# Sheet1.net
KiCad netlist of a schematic drawn in Altium Designer
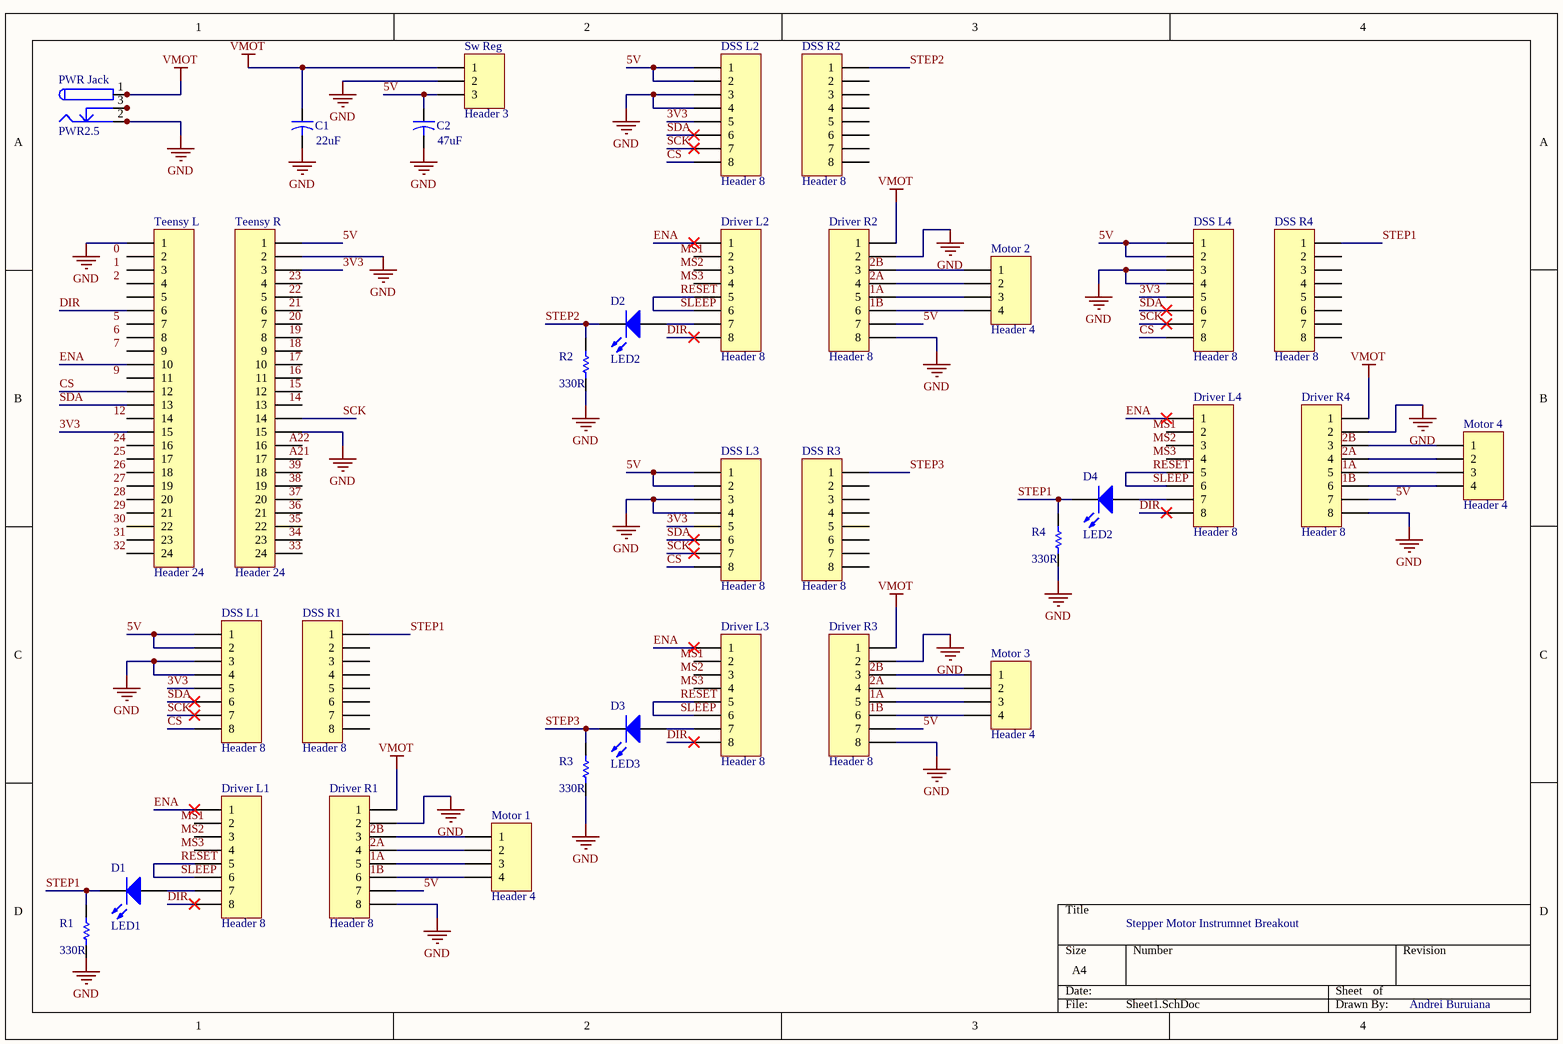
[diagram p0: Sheet1.SchDoc]

(export (version "E")
  (design (tool "Eeschema 10.0.6"))
  (components
    (comp (ref "C1")
      (value "22uF")
      (footprint "CAPR5-4X5")
      (description "Capacitor")
      (fields (field (name "PUBLISHER") "Altium Limited"))
      (libsource (lib "Miscellaneous Devices") (part "Cap2"))
    )
    (comp (ref "C2")
      (value "47uF")
      (footprint "CAPR5-4X5")
      (description "Capacitor")
      (fields (field (name "PUBLISHER") "Altium Limited"))
      (libsource (lib "Miscellaneous Devices") (part "Cap2"))
    )
    (comp (ref "D1")
      (value "LED1")
      (footprint "3.2X1.6X1.1")
      (description "Typical RED, GREEN, YELLOW, AMBER GaAs LED")
      (fields (field (name "PUBLISHER") "Altium Limited"))
      (libsource (lib "Miscellaneous Devices") (part "LED2"))
    )
    (comp (ref "D2")
      (value "LED2")
      (footprint "3.2X1.6X1.1")
      (description "Typical RED, GREEN, YELLOW, AMBER GaAs LED")
      (fields (field (name "PUBLISHER") "Altium Limited"))
      (libsource (lib "Miscellaneous Devices") (part "LED2"))
    )
    (comp (ref "D3")
      (value "LED3")
      (footprint "3.2X1.6X1.1")
      (description "Typical RED, GREEN, YELLOW, AMBER GaAs LED")
      (fields (field (name "PUBLISHER") "Altium Limited"))
      (libsource (lib "Miscellaneous Devices") (part "LED2"))
    )
    (comp (ref "D4")
      (value "LED2")
      (footprint "3.2X1.6X1.1")
      (description "Typical RED, GREEN, YELLOW, AMBER GaAs LED")
      (fields (field (name "PUBLISHER") "Altium Limited"))
      (libsource (lib "Miscellaneous Devices") (part "LED2"))
    )
    (comp (ref "Driver L1")
      (value "Header 8")
      (footprint "HDR1X8")
      (description "Header, 8-Pin")
      (fields (field (name "PUBLISHER") "Altium Limited"))
      (libsource (lib "") (part "Header 8_1"))
    )
    (comp (ref "Driver L2")
      (value "Header 8")
      (footprint "HDR1X8")
      (description "Header, 8-Pin")
      (fields (field (name "PUBLISHER") "Altium Limited"))
      (libsource (lib "") (part "Header 8_1"))
    )
    (comp (ref "Driver L3")
      (value "Header 8")
      (footprint "HDR1X8")
      (description "Header, 8-Pin")
      (fields (field (name "PUBLISHER") "Altium Limited"))
      (libsource (lib "") (part "Header 8_1"))
    )
    (comp (ref "Driver L4")
      (value "Header 8")
      (footprint "HDR1X8")
      (description "Header, 8-Pin")
      (fields (field (name "PUBLISHER") "Altium Limited"))
      (libsource (lib "") (part "Header 8_1"))
    )
    (comp (ref "Driver R1")
      (value "Header 8")
      (footprint "HDR1X8")
      (description "Header, 8-Pin")
      (fields (field (name "PUBLISHER") "Altium Limited"))
      (libsource (lib "Miscellaneous Connectors") (part "Header 8"))
    )
    (comp (ref "Driver R2")
      (value "Header 8")
      (footprint "HDR1X8")
      (description "Header, 8-Pin")
      (fields (field (name "PUBLISHER") "Altium Limited"))
      (libsource (lib "Miscellaneous Connectors") (part "Header 8"))
    )
    (comp (ref "Driver R3")
      (value "Header 8")
      (footprint "HDR1X8")
      (description "Header, 8-Pin")
      (fields (field (name "PUBLISHER") "Altium Limited"))
      (libsource (lib "Miscellaneous Connectors") (part "Header 8"))
    )
    (comp (ref "Driver R4")
      (value "Header 8")
      (footprint "HDR1X8")
      (description "Header, 8-Pin")
      (fields (field (name "PUBLISHER") "Altium Limited"))
      (libsource (lib "Miscellaneous Connectors") (part "Header 8"))
    )
    (comp (ref "DSS L1")
      (value "Header 8")
      (footprint "HDR1X8")
      (description "Header, 8-Pin")
      (fields (field (name "PUBLISHER") "Altium Limited"))
      (libsource (lib "") (part "Header 8_1"))
    )
    (comp (ref "DSS L2")
      (value "Header 8")
      (footprint "HDR1X8")
      (description "Header, 8-Pin")
      (fields (field (name "PUBLISHER") "Altium Limited"))
      (libsource (lib "") (part "Header 8_1"))
    )
    (comp (ref "DSS L3")
      (value "Header 8")
      (footprint "HDR1X8")
      (description "Header, 8-Pin")
      (fields (field (name "PUBLISHER") "Altium Limited"))
      (libsource (lib "") (part "Header 8_1"))
    )
    (comp (ref "DSS L4")
      (value "Header 8")
      (footprint "HDR1X8")
      (description "Header, 8-Pin")
      (fields (field (name "PUBLISHER") "Altium Limited"))
      (libsource (lib "") (part "Header 8_1"))
    )
    (comp (ref "DSS R1")
      (value "Header 8")
      (footprint "HDR1X8")
      (description "Header, 8-Pin")
      (fields (field (name "PUBLISHER") "Altium Limited"))
      (libsource (lib "Miscellaneous Connectors") (part "Header 8"))
    )
    (comp (ref "DSS R2")
      (value "Header 8")
      (footprint "HDR1X8")
      (description "Header, 8-Pin")
      (fields (field (name "PUBLISHER") "Altium Limited"))
      (libsource (lib "Miscellaneous Connectors") (part "Header 8"))
    )
    (comp (ref "DSS R3")
      (value "Header 8")
      (footprint "HDR1X8")
      (description "Header, 8-Pin")
      (fields (field (name "PUBLISHER") "Altium Limited"))
      (libsource (lib "Miscellaneous Connectors") (part "Header 8"))
    )
    (comp (ref "DSS R4")
      (value "Header 8")
      (footprint "HDR1X8")
      (description "Header, 8-Pin")
      (fields (field (name "PUBLISHER") "Altium Limited"))
      (libsource (lib "Miscellaneous Connectors") (part "Header 8"))
    )
    (comp (ref "Motor 1")
      (value "Header 4")
      (footprint "HDR1X4")
      (description "Header, 4-Pin")
      (fields (field (name "PUBLISHER") "Altium Limited"))
      (libsource (lib "Miscellaneous Connectors") (part "Header 4"))
    )
    (comp (ref "Motor 2")
      (value "Header 4")
      (footprint "HDR1X4")
      (description "Header, 4-Pin")
      (fields (field (name "PUBLISHER") "Altium Limited"))
      (libsource (lib "Miscellaneous Connectors") (part "Header 4"))
    )
    (comp (ref "Motor 3")
      (value "Header 4")
      (footprint "HDR1X4")
      (description "Header, 4-Pin")
      (fields (field (name "PUBLISHER") "Altium Limited"))
      (libsource (lib "Miscellaneous Connectors") (part "Header 4"))
    )
    (comp (ref "Motor 4")
      (value "Header 4")
      (footprint "HDR1X4")
      (description "Header, 4-Pin")
      (fields (field (name "PUBLISHER") "Altium Limited"))
      (libsource (lib "Miscellaneous Connectors") (part "Header 4"))
    )
    (comp (ref "PWR Jack")
      (value "PWR2.5")
      (footprint "KLD-0202")
      (description "Low Voltage Power Supply Connector")
      (fields (field (name "PUBLISHER") "Altium Limited"))
      (libsource (lib "Miscellaneous Connectors") (part "PWR2.5"))
    )
    (comp (ref "R1")
      (value "330R")
      (footprint "AXIAL-0.5")
      (description "Semiconductor Resistor")
      (fields (field (name "PUBLISHER") "Altium Limited"))
      (libsource (lib "Miscellaneous Devices") (part "Res Semi"))
    )
    (comp (ref "R2")
      (value "330R")
      (footprint "AXIAL-0.5")
      (description "Semiconductor Resistor")
      (fields (field (name "PUBLISHER") "Altium Limited"))
      (libsource (lib "Miscellaneous Devices") (part "Res Semi"))
    )
    (comp (ref "R3")
      (value "330R")
      (footprint "AXIAL-0.5")
      (description "Semiconductor Resistor")
      (fields (field (name "PUBLISHER") "Altium Limited"))
      (libsource (lib "Miscellaneous Devices") (part "Res Semi"))
    )
    (comp (ref "R4")
      (value "330R")
      (footprint "AXIAL-0.5")
      (description "Semiconductor Resistor")
      (fields (field (name "PUBLISHER") "Altium Limited"))
      (libsource (lib "Miscellaneous Devices") (part "Res Semi"))
    )
    (comp (ref "Sw Reg")
      (value "Header 3")
      (footprint "HDR1X3")
      (description "Header, 3-Pin")
      (fields (field (name "PUBLISHER") "Altium Limited"))
      (libsource (lib "Miscellaneous Connectors") (part "Header 3"))
    )
    (comp (ref "Teensy L")
      (value "Header 24")
      (footprint "HDR1X24")
      (description "Header, 24-Pin")
      (fields (field (name "PUBLISHER") "Altium Limited"))
      (libsource (lib "Miscellaneous Connectors") (part "Header 24"))
    )
    (comp (ref "Teensy R")
      (value "Header 24")
      (footprint "HDR1X24")
      (description "Header, 24-Pin")
      (fields (field (name "PUBLISHER") "Altium Limited"))
      (libsource (lib "") (part "Header 24_1"))
    )
  )
  (nets
    (net (code "8") (name "/3V3") (class "Default")
      (node (ref "DSS L1") (pin "5") (pinfunction "5_5") (pintype "passive"))
      (node (ref "DSS L2") (pin "5") (pinfunction "5_5") (pintype "passive"))
      (node (ref "DSS L3") (pin "5") (pinfunction "5_5") (pintype "passive"))
      (node (ref "DSS L4") (pin "5") (pinfunction "5_5") (pintype "passive"))
      (node (ref "Teensy L") (pin "15") (pinfunction "15_15") (pintype "passive"))
      (node (ref "Teensy R") (pin "3") (pinfunction "3_3") (pintype "passive"))
    )
    (net (code "10") (name "/5V") (class "Default")
      (node (ref "C2") (pin "1") (pinfunction "1_1") (pintype "passive"))
      (node (ref "DSS L1") (pin "1") (pinfunction "1_1") (pintype "passive"))
      (node (ref "DSS L1") (pin "2") (pinfunction "2_2") (pintype "passive"))
      (node (ref "DSS L2") (pin "1") (pinfunction "1_1") (pintype "passive"))
      (node (ref "DSS L2") (pin "2") (pinfunction "2_2") (pintype "passive"))
      (node (ref "DSS L3") (pin "1") (pinfunction "1_1") (pintype "passive"))
      (node (ref "DSS L3") (pin "2") (pinfunction "2_2") (pintype "passive"))
      (node (ref "DSS L4") (pin "1") (pinfunction "1_1") (pintype "passive"))
      (node (ref "DSS L4") (pin "2") (pinfunction "2_2") (pintype "passive"))
      (node (ref "Driver R1") (pin "7") (pinfunction "7_7") (pintype "passive"))
      (node (ref "Driver R2") (pin "7") (pinfunction "7_7") (pintype "passive"))
      (node (ref "Driver R3") (pin "7") (pinfunction "7_7") (pintype "passive"))
      (node (ref "Driver R4") (pin "7") (pinfunction "7_7") (pintype "passive"))
      (node (ref "Sw Reg") (pin "3") (pinfunction "3_3") (pintype "passive"))
      (node (ref "Teensy R") (pin "1") (pinfunction "1_1") (pintype "passive"))
    )
    (net (code "43") (name "/CS") (class "Default")
      (node (ref "DSS L1") (pin "8") (pinfunction "8_8") (pintype "passive"))
      (node (ref "DSS L2") (pin "8") (pinfunction "8_8") (pintype "passive"))
      (node (ref "DSS L3") (pin "8") (pinfunction "8_8") (pintype "passive"))
      (node (ref "DSS L4") (pin "8") (pinfunction "8_8") (pintype "passive"))
      (node (ref "Teensy L") (pin "12") (pinfunction "12_12") (pintype "passive"))
    )
    (net (code "44") (name "/DIR") (class "Default")
      (node (ref "Driver L1") (pin "8") (pinfunction "8_8") (pintype "passive"))
      (node (ref "Driver L2") (pin "8") (pinfunction "8_8") (pintype "passive"))
      (node (ref "Driver L3") (pin "8") (pinfunction "8_8") (pintype "passive"))
      (node (ref "Driver L4") (pin "8") (pinfunction "8_8") (pintype "passive"))
      (node (ref "Teensy L") (pin "6") (pinfunction "6_6") (pintype "passive"))
    )
    (net (code "45") (name "/ENA") (class "Default")
      (node (ref "Driver L1") (pin "1") (pinfunction "1_1") (pintype "passive"))
      (node (ref "Driver L2") (pin "1") (pinfunction "1_1") (pintype "passive"))
      (node (ref "Driver L3") (pin "1") (pinfunction "1_1") (pintype "passive"))
      (node (ref "Driver L4") (pin "1") (pinfunction "1_1") (pintype "passive"))
      (node (ref "Teensy L") (pin "10") (pinfunction "10_10") (pintype "passive"))
    )
    (net (code "49") (name "/RESET") (class "Default")
      (node (ref "Driver L1") (pin "5") (pinfunction "5_5") (pintype "passive"))
      (node (ref "Driver L1") (pin "6") (pinfunction "6_6") (pintype "passive"))
      (node (ref "Driver L2") (pin "5") (pinfunction "5_5") (pintype "passive"))
      (node (ref "Driver L2") (pin "6") (pinfunction "6_6") (pintype "passive"))
      (node (ref "Driver L3") (pin "5") (pinfunction "5_5") (pintype "passive"))
      (node (ref "Driver L3") (pin "6") (pinfunction "6_6") (pintype "passive"))
      (node (ref "Driver L4") (pin "5") (pinfunction "5_5") (pintype "passive"))
      (node (ref "Driver L4") (pin "6") (pinfunction "6_6") (pintype "passive"))
    )
    (net (code "50") (name "/SCK") (class "Default")
      (node (ref "DSS L1") (pin "7") (pinfunction "7_7") (pintype "passive"))
      (node (ref "DSS L2") (pin "7") (pinfunction "7_7") (pintype "passive"))
      (node (ref "DSS L3") (pin "7") (pinfunction "7_7") (pintype "passive"))
      (node (ref "DSS L4") (pin "7") (pinfunction "7_7") (pintype "passive"))
      (node (ref "Teensy R") (pin "14") (pinfunction "14_14") (pintype "passive"))
    )
    (net (code "51") (name "/SDA") (class "Default")
      (node (ref "DSS L1") (pin "6") (pinfunction "6_6") (pintype "passive"))
      (node (ref "DSS L2") (pin "6") (pinfunction "6_6") (pintype "passive"))
      (node (ref "DSS L3") (pin "6") (pinfunction "6_6") (pintype "passive"))
      (node (ref "DSS L4") (pin "6") (pinfunction "6_6") (pintype "passive"))
      (node (ref "Teensy L") (pin "13") (pinfunction "13_13") (pintype "passive"))
    )
    (net (code "52") (name "/STEP1") (class "Default")
      (node (ref "D1") (pin "2") (pinfunction "K_2") (pintype "passive"))
      (node (ref "D4") (pin "2") (pinfunction "K_2") (pintype "passive"))
      (node (ref "DSS R1") (pin "1") (pinfunction "1_1") (pintype "passive"))
      (node (ref "DSS R4") (pin "1") (pinfunction "1_1") (pintype "passive"))
      (node (ref "R1") (pin "2") (pinfunction "2_2") (pintype "passive"))
      (node (ref "R4") (pin "2") (pinfunction "2_2") (pintype "passive"))
    )
    (net (code "53") (name "/STEP2") (class "Default")
      (node (ref "D2") (pin "2") (pinfunction "K_2") (pintype "passive"))
      (node (ref "DSS R2") (pin "1") (pinfunction "1_1") (pintype "passive"))
      (node (ref "R2") (pin "2") (pinfunction "2_2") (pintype "passive"))
    )
    (net (code "54") (name "/STEP3") (class "Default")
      (node (ref "D3") (pin "2") (pinfunction "K_2") (pintype "passive"))
      (node (ref "DSS R3") (pin "1") (pinfunction "1_1") (pintype "passive"))
      (node (ref "R3") (pin "2") (pinfunction "2_2") (pintype "passive"))
    )
    (net (code "55") (name "GND") (class "Default")
      (node (ref "C1") (pin "2") (pinfunction "2_2") (pintype "passive"))
      (node (ref "C2") (pin "2") (pinfunction "2_2") (pintype "passive"))
      (node (ref "DSS L1") (pin "3") (pinfunction "3_3") (pintype "passive"))
      (node (ref "DSS L1") (pin "4") (pinfunction "4_4") (pintype "passive"))
      (node (ref "DSS L2") (pin "3") (pinfunction "3_3") (pintype "passive"))
      (node (ref "DSS L2") (pin "4") (pinfunction "4_4") (pintype "passive"))
      (node (ref "DSS L3") (pin "3") (pinfunction "3_3") (pintype "passive"))
      (node (ref "DSS L3") (pin "4") (pinfunction "4_4") (pintype "passive"))
      (node (ref "DSS L4") (pin "3") (pinfunction "3_3") (pintype "passive"))
      (node (ref "DSS L4") (pin "4") (pinfunction "4_4") (pintype "passive"))
      (node (ref "Driver R1") (pin "2") (pinfunction "2_2") (pintype "passive"))
      (node (ref "Driver R1") (pin "8") (pinfunction "8_8") (pintype "passive"))
      (node (ref "Driver R2") (pin "2") (pinfunction "2_2") (pintype "passive"))
      (node (ref "Driver R2") (pin "8") (pinfunction "8_8") (pintype "passive"))
      (node (ref "Driver R3") (pin "2") (pinfunction "2_2") (pintype "passive"))
      (node (ref "Driver R3") (pin "8") (pinfunction "8_8") (pintype "passive"))
      (node (ref "Driver R4") (pin "2") (pinfunction "2_2") (pintype "passive"))
      (node (ref "Driver R4") (pin "8") (pinfunction "8_8") (pintype "passive"))
      (node (ref "PWR Jack") (pin "2") (pinfunction "2_2") (pintype "power_in"))
      (node (ref "PWR Jack") (pin "2A") (pinfunction "2A_2A") (pintype "power_in"))
      (node (ref "PWR Jack") (pin "2B") (pinfunction "2B_2B") (pintype "power_in"))
      (node (ref "R1") (pin "1") (pinfunction "1_1") (pintype "passive"))
      (node (ref "R2") (pin "1") (pinfunction "1_1") (pintype "passive"))
      (node (ref "R3") (pin "1") (pinfunction "1_1") (pintype "passive"))
      (node (ref "R4") (pin "1") (pinfunction "1_1") (pintype "passive"))
      (node (ref "Sw Reg") (pin "2") (pinfunction "2_2") (pintype "passive"))
      (node (ref "Teensy L") (pin "1") (pinfunction "1_1") (pintype "passive"))
      (node (ref "Teensy R") (pin "15") (pinfunction "15_15") (pintype "passive"))
      (node (ref "Teensy R") (pin "2") (pinfunction "2_2") (pintype "passive"))
    )
    (net (code "56") (name "Net-(D1-A)") (class "Default")
      (node (ref "D1") (pin "1") (pinfunction "A_1") (pintype "passive"))
      (node (ref "Driver L1") (pin "7") (pinfunction "7_7") (pintype "passive"))
    )
    (net (code "57") (name "Net-(D2-A)") (class "Default")
      (node (ref "D2") (pin "1") (pinfunction "A_1") (pintype "passive"))
      (node (ref "Driver L2") (pin "7") (pinfunction "7_7") (pintype "passive"))
    )
    (net (code "58") (name "Net-(D3-A)") (class "Default")
      (node (ref "D3") (pin "1") (pinfunction "A_1") (pintype "passive"))
      (node (ref "Driver L3") (pin "7") (pinfunction "7_7") (pintype "passive"))
    )
    (net (code "59") (name "Net-(D4-A)") (class "Default")
      (node (ref "D4") (pin "1") (pinfunction "A_1") (pintype "passive"))
      (node (ref "Driver L4") (pin "7") (pinfunction "7_7") (pintype "passive"))
    )
    (net (code "60") (name "Net-(Driver R1-Pad3)") (class "Default")
      (node (ref "Driver R1") (pin "3") (pinfunction "3_3") (pintype "passive"))
      (node (ref "Motor 1") (pin "1") (pinfunction "1_1") (pintype "passive"))
    )
    (net (code "61") (name "Net-(Driver R1-Pad4)") (class "Default")
      (node (ref "Driver R1") (pin "4") (pinfunction "4_4") (pintype "passive"))
      (node (ref "Motor 1") (pin "2") (pinfunction "2_2") (pintype "passive"))
    )
    (net (code "62") (name "Net-(Driver R1-Pad5)") (class "Default")
      (node (ref "Driver R1") (pin "5") (pinfunction "5_5") (pintype "passive"))
      (node (ref "Motor 1") (pin "3") (pinfunction "3_3") (pintype "passive"))
    )
    (net (code "63") (name "Net-(Driver R1-Pad6)") (class "Default")
      (node (ref "Driver R1") (pin "6") (pinfunction "6_6") (pintype "passive"))
      (node (ref "Motor 1") (pin "4") (pinfunction "4_4") (pintype "passive"))
    )
    (net (code "64") (name "Net-(Driver R2-Pad3)") (class "Default")
      (node (ref "Driver R2") (pin "3") (pinfunction "3_3") (pintype "passive"))
      (node (ref "Motor 2") (pin "1") (pinfunction "1_1") (pintype "passive"))
    )
    (net (code "65") (name "Net-(Driver R2-Pad4)") (class "Default")
      (node (ref "Driver R2") (pin "4") (pinfunction "4_4") (pintype "passive"))
      (node (ref "Motor 2") (pin "2") (pinfunction "2_2") (pintype "passive"))
    )
    (net (code "66") (name "Net-(Driver R2-Pad5)") (class "Default")
      (node (ref "Driver R2") (pin "5") (pinfunction "5_5") (pintype "passive"))
      (node (ref "Motor 2") (pin "3") (pinfunction "3_3") (pintype "passive"))
    )
    (net (code "67") (name "Net-(Driver R2-Pad6)") (class "Default")
      (node (ref "Driver R2") (pin "6") (pinfunction "6_6") (pintype "passive"))
      (node (ref "Motor 2") (pin "4") (pinfunction "4_4") (pintype "passive"))
    )
    (net (code "68") (name "Net-(Driver R3-Pad3)") (class "Default")
      (node (ref "Driver R3") (pin "3") (pinfunction "3_3") (pintype "passive"))
      (node (ref "Motor 3") (pin "1") (pinfunction "1_1") (pintype "passive"))
    )
    (net (code "69") (name "Net-(Driver R3-Pad4)") (class "Default")
      (node (ref "Driver R3") (pin "4") (pinfunction "4_4") (pintype "passive"))
      (node (ref "Motor 3") (pin "2") (pinfunction "2_2") (pintype "passive"))
    )
    (net (code "70") (name "Net-(Driver R3-Pad5)") (class "Default")
      (node (ref "Driver R3") (pin "5") (pinfunction "5_5") (pintype "passive"))
      (node (ref "Motor 3") (pin "3") (pinfunction "3_3") (pintype "passive"))
    )
    (net (code "71") (name "Net-(Driver R3-Pad6)") (class "Default")
      (node (ref "Driver R3") (pin "6") (pinfunction "6_6") (pintype "passive"))
      (node (ref "Motor 3") (pin "4") (pinfunction "4_4") (pintype "passive"))
    )
    (net (code "72") (name "Net-(Driver R4-Pad3)") (class "Default")
      (node (ref "Driver R4") (pin "3") (pinfunction "3_3") (pintype "passive"))
      (node (ref "Motor 4") (pin "1") (pinfunction "1_1") (pintype "passive"))
    )
    (net (code "73") (name "Net-(Driver R4-Pad4)") (class "Default")
      (node (ref "Driver R4") (pin "4") (pinfunction "4_4") (pintype "passive"))
      (node (ref "Motor 4") (pin "2") (pinfunction "2_2") (pintype "passive"))
    )
    (net (code "74") (name "Net-(Driver R4-Pad5)") (class "Default")
      (node (ref "Driver R4") (pin "5") (pinfunction "5_5") (pintype "passive"))
      (node (ref "Motor 4") (pin "3") (pinfunction "3_3") (pintype "passive"))
    )
    (net (code "75") (name "Net-(Driver R4-Pad6)") (class "Default")
      (node (ref "Driver R4") (pin "6") (pinfunction "6_6") (pintype "passive"))
      (node (ref "Motor 4") (pin "4") (pinfunction "4_4") (pintype "passive"))
    )
    (net (code "76") (name "Net-(PWR Jack-Pad3)") (class "Default")
      (node (ref "PWR Jack") (pin "3") (pinfunction "3_3") (pintype "power_in"))
      (node (ref "PWR Jack") (pin "3A") (pinfunction "3A_3A") (pintype "power_in"))
      (node (ref "PWR Jack") (pin "3B") (pinfunction "3B_3B") (pintype "power_in"))
    )
    (net (code "77") (name "VMOT") (class "Default")
      (node (ref "C1") (pin "1") (pinfunction "1_1") (pintype "passive"))
      (node (ref "Driver R1") (pin "1") (pinfunction "1_1") (pintype "passive"))
      (node (ref "Driver R2") (pin "1") (pinfunction "1_1") (pintype "passive"))
      (node (ref "Driver R3") (pin "1") (pinfunction "1_1") (pintype "passive"))
      (node (ref "Driver R4") (pin "1") (pinfunction "1_1") (pintype "passive"))
      (node (ref "PWR Jack") (pin "1") (pinfunction "1_1") (pintype "power_in"))
      (node (ref "PWR Jack") (pin "1A") (pinfunction "1A_1A") (pintype "power_in"))
      (node (ref "PWR Jack") (pin "1B") (pinfunction "1B_1B") (pintype "power_in"))
      (node (ref "Sw Reg") (pin "1") (pinfunction "1_1") (pintype "passive"))
    )
    (net (code "78") (name "unconnected-(DSS R1-Pad2)") (class "Default")
      (node (ref "DSS R1") (pin "2") (pinfunction "2_2") (pintype "passive"))
    )
    (net (code "79") (name "unconnected-(DSS R1-Pad3)") (class "Default")
      (node (ref "DSS R1") (pin "3") (pinfunction "3_3") (pintype "passive"))
    )
    (net (code "80") (name "unconnected-(DSS R1-Pad4)") (class "Default")
      (node (ref "DSS R1") (pin "4") (pinfunction "4_4") (pintype "passive"))
    )
    (net (code "81") (name "unconnected-(DSS R1-Pad5)") (class "Default")
      (node (ref "DSS R1") (pin "5") (pinfunction "5_5") (pintype "passive"))
    )
    (net (code "82") (name "unconnected-(DSS R1-Pad6)") (class "Default")
      (node (ref "DSS R1") (pin "6") (pinfunction "6_6") (pintype "passive"))
    )
    (net (code "83") (name "unconnected-(DSS R1-Pad7)") (class "Default")
      (node (ref "DSS R1") (pin "7") (pinfunction "7_7") (pintype "passive"))
    )
    (net (code "84") (name "unconnected-(DSS R1-Pad8)") (class "Default")
      (node (ref "DSS R1") (pin "8") (pinfunction "8_8") (pintype "passive"))
    )
    (net (code "85") (name "unconnected-(DSS R2-Pad2)") (class "Default")
      (node (ref "DSS R2") (pin "2") (pinfunction "2_2") (pintype "passive"))
    )
    (net (code "86") (name "unconnected-(DSS R2-Pad3)") (class "Default")
      (node (ref "DSS R2") (pin "3") (pinfunction "3_3") (pintype "passive"))
    )
    (net (code "87") (name "unconnected-(DSS R2-Pad4)") (class "Default")
      (node (ref "DSS R2") (pin "4") (pinfunction "4_4") (pintype "passive"))
    )
    (net (code "88") (name "unconnected-(DSS R2-Pad5)") (class "Default")
      (node (ref "DSS R2") (pin "5") (pinfunction "5_5") (pintype "passive"))
    )
    (net (code "89") (name "unconnected-(DSS R2-Pad6)") (class "Default")
      (node (ref "DSS R2") (pin "6") (pinfunction "6_6") (pintype "passive"))
    )
    (net (code "90") (name "unconnected-(DSS R2-Pad7)") (class "Default")
      (node (ref "DSS R2") (pin "7") (pinfunction "7_7") (pintype "passive"))
    )
    (net (code "91") (name "unconnected-(DSS R2-Pad8)") (class "Default")
      (node (ref "DSS R2") (pin "8") (pinfunction "8_8") (pintype "passive"))
    )
    (net (code "92") (name "unconnected-(DSS R3-Pad2)") (class "Default")
      (node (ref "DSS R3") (pin "2") (pinfunction "2_2") (pintype "passive"))
    )
    (net (code "93") (name "unconnected-(DSS R3-Pad3)") (class "Default")
      (node (ref "DSS R3") (pin "3") (pinfunction "3_3") (pintype "passive"))
    )
    (net (code "94") (name "unconnected-(DSS R3-Pad4)") (class "Default")
      (node (ref "DSS R3") (pin "4") (pinfunction "4_4") (pintype "passive"))
    )
    (net (code "95") (name "unconnected-(DSS R3-Pad5)") (class "Default")
      (node (ref "DSS R3") (pin "5") (pinfunction "5_5") (pintype "passive"))
    )
    (net (code "96") (name "unconnected-(DSS R3-Pad6)") (class "Default")
      (node (ref "DSS R3") (pin "6") (pinfunction "6_6") (pintype "passive"))
    )
    (net (code "97") (name "unconnected-(DSS R3-Pad7)") (class "Default")
      (node (ref "DSS R3") (pin "7") (pinfunction "7_7") (pintype "passive"))
    )
    (net (code "98") (name "unconnected-(DSS R3-Pad8)") (class "Default")
      (node (ref "DSS R3") (pin "8") (pinfunction "8_8") (pintype "passive"))
    )
    (net (code "99") (name "unconnected-(DSS R4-Pad2)") (class "Default")
      (node (ref "DSS R4") (pin "2") (pinfunction "2_2") (pintype "passive"))
    )
    (net (code "100") (name "unconnected-(DSS R4-Pad3)") (class "Default")
      (node (ref "DSS R4") (pin "3") (pinfunction "3_3") (pintype "passive"))
    )
    (net (code "101") (name "unconnected-(DSS R4-Pad4)") (class "Default")
      (node (ref "DSS R4") (pin "4") (pinfunction "4_4") (pintype "passive"))
    )
    (net (code "102") (name "unconnected-(DSS R4-Pad5)") (class "Default")
      (node (ref "DSS R4") (pin "5") (pinfunction "5_5") (pintype "passive"))
    )
    (net (code "103") (name "unconnected-(DSS R4-Pad6)") (class "Default")
      (node (ref "DSS R4") (pin "6") (pinfunction "6_6") (pintype "passive"))
    )
    (net (code "104") (name "unconnected-(DSS R4-Pad7)") (class "Default")
      (node (ref "DSS R4") (pin "7") (pinfunction "7_7") (pintype "passive"))
    )
    (net (code "105") (name "unconnected-(DSS R4-Pad8)") (class "Default")
      (node (ref "DSS R4") (pin "8") (pinfunction "8_8") (pintype "passive"))
    )
    (net (code "106") (name "unconnected-(Driver L1-Pad2)") (class "Default")
      (node (ref "Driver L1") (pin "2") (pinfunction "2_2") (pintype "passive"))
    )
    (net (code "107") (name "unconnected-(Driver L1-Pad3)") (class "Default")
      (node (ref "Driver L1") (pin "3") (pinfunction "3_3") (pintype "passive"))
    )
    (net (code "108") (name "unconnected-(Driver L1-Pad4)") (class "Default")
      (node (ref "Driver L1") (pin "4") (pinfunction "4_4") (pintype "passive"))
    )
    (net (code "109") (name "unconnected-(Driver L2-Pad2)") (class "Default")
      (node (ref "Driver L2") (pin "2") (pinfunction "2_2") (pintype "passive"))
    )
    (net (code "110") (name "unconnected-(Driver L2-Pad3)") (class "Default")
      (node (ref "Driver L2") (pin "3") (pinfunction "3_3") (pintype "passive"))
    )
    (net (code "111") (name "unconnected-(Driver L2-Pad4)") (class "Default")
      (node (ref "Driver L2") (pin "4") (pinfunction "4_4") (pintype "passive"))
    )
    (net (code "112") (name "unconnected-(Driver L3-Pad2)") (class "Default")
      (node (ref "Driver L3") (pin "2") (pinfunction "2_2") (pintype "passive"))
    )
    (net (code "113") (name "unconnected-(Driver L3-Pad3)") (class "Default")
      (node (ref "Driver L3") (pin "3") (pinfunction "3_3") (pintype "passive"))
    )
    (net (code "114") (name "unconnected-(Driver L3-Pad4)") (class "Default")
      (node (ref "Driver L3") (pin "4") (pinfunction "4_4") (pintype "passive"))
    )
    (net (code "115") (name "unconnected-(Driver L4-Pad2)") (class "Default")
      (node (ref "Driver L4") (pin "2") (pinfunction "2_2") (pintype "passive"))
    )
    (net (code "116") (name "unconnected-(Driver L4-Pad3)") (class "Default")
      (node (ref "Driver L4") (pin "3") (pinfunction "3_3") (pintype "passive"))
    )
    (net (code "117") (name "unconnected-(Driver L4-Pad4)") (class "Default")
      (node (ref "Driver L4") (pin "4") (pinfunction "4_4") (pintype "passive"))
    )
    (net (code "118") (name "unconnected-(Teensy L-Pad2)") (class "Default")
      (node (ref "Teensy L") (pin "2") (pinfunction "2_2") (pintype "passive"))
    )
    (net (code "119") (name "unconnected-(Teensy L-Pad3)") (class "Default")
      (node (ref "Teensy L") (pin "3") (pinfunction "3_3") (pintype "passive"))
    )
    (net (code "120") (name "unconnected-(Teensy L-Pad4)") (class "Default")
      (node (ref "Teensy L") (pin "4") (pinfunction "4_4") (pintype "passive"))
    )
    (net (code "121") (name "unconnected-(Teensy L-Pad5)") (class "Default")
      (node (ref "Teensy L") (pin "5") (pinfunction "5_5") (pintype "passive"))
    )
    (net (code "122") (name "unconnected-(Teensy L-Pad7)") (class "Default")
      (node (ref "Teensy L") (pin "7") (pinfunction "7_7") (pintype "passive"))
    )
    (net (code "123") (name "unconnected-(Teensy L-Pad8)") (class "Default")
      (node (ref "Teensy L") (pin "8") (pinfunction "8_8") (pintype "passive"))
    )
    (net (code "124") (name "unconnected-(Teensy L-Pad9)") (class "Default")
      (node (ref "Teensy L") (pin "9") (pinfunction "9_9") (pintype "passive"))
    )
    (net (code "125") (name "unconnected-(Teensy L-Pad11)") (class "Default")
      (node (ref "Teensy L") (pin "11") (pinfunction "11_11") (pintype "passive"))
    )
    (net (code "126") (name "unconnected-(Teensy L-Pad14)") (class "Default")
      (node (ref "Teensy L") (pin "14") (pinfunction "14_14") (pintype "passive"))
    )
    (net (code "127") (name "unconnected-(Teensy L-Pad16)") (class "Default")
      (node (ref "Teensy L") (pin "16") (pinfunction "16_16") (pintype "passive"))
    )
    (net (code "128") (name "unconnected-(Teensy L-Pad17)") (class "Default")
      (node (ref "Teensy L") (pin "17") (pinfunction "17_17") (pintype "passive"))
    )
    (net (code "129") (name "unconnected-(Teensy L-Pad18)") (class "Default")
      (node (ref "Teensy L") (pin "18") (pinfunction "18_18") (pintype "passive"))
    )
    (net (code "130") (name "unconnected-(Teensy L-Pad19)") (class "Default")
      (node (ref "Teensy L") (pin "19") (pinfunction "19_19") (pintype "passive"))
    )
    (net (code "131") (name "unconnected-(Teensy L-Pad20)") (class "Default")
      (node (ref "Teensy L") (pin "20") (pinfunction "20_20") (pintype "passive"))
    )
    (net (code "132") (name "unconnected-(Teensy L-Pad21)") (class "Default")
      (node (ref "Teensy L") (pin "21") (pinfunction "21_21") (pintype "passive"))
    )
    (net (code "133") (name "unconnected-(Teensy L-Pad22)") (class "Default")
      (node (ref "Teensy L") (pin "22") (pinfunction "22_22") (pintype "passive"))
    )
    (net (code "134") (name "unconnected-(Teensy L-Pad23)") (class "Default")
      (node (ref "Teensy L") (pin "23") (pinfunction "23_23") (pintype "passive"))
    )
    (net (code "135") (name "unconnected-(Teensy L-Pad24)") (class "Default")
      (node (ref "Teensy L") (pin "24") (pinfunction "24_24") (pintype "passive"))
    )
    (net (code "136") (name "unconnected-(Teensy R-Pad4)") (class "Default")
      (node (ref "Teensy R") (pin "4") (pinfunction "4_4") (pintype "passive"))
    )
    (net (code "137") (name "unconnected-(Teensy R-Pad5)") (class "Default")
      (node (ref "Teensy R") (pin "5") (pinfunction "5_5") (pintype "passive"))
    )
    (net (code "138") (name "unconnected-(Teensy R-Pad6)") (class "Default")
      (node (ref "Teensy R") (pin "6") (pinfunction "6_6") (pintype "passive"))
    )
    (net (code "139") (name "unconnected-(Teensy R-Pad7)") (class "Default")
      (node (ref "Teensy R") (pin "7") (pinfunction "7_7") (pintype "passive"))
    )
    (net (code "140") (name "unconnected-(Teensy R-Pad8)") (class "Default")
      (node (ref "Teensy R") (pin "8") (pinfunction "8_8") (pintype "passive"))
    )
    (net (code "141") (name "unconnected-(Teensy R-Pad9)") (class "Default")
      (node (ref "Teensy R") (pin "9") (pinfunction "9_9") (pintype "passive"))
    )
    (net (code "142") (name "unconnected-(Teensy R-Pad10)") (class "Default")
      (node (ref "Teensy R") (pin "10") (pinfunction "10_10") (pintype "passive"))
    )
    (net (code "143") (name "unconnected-(Teensy R-Pad11)") (class "Default")
      (node (ref "Teensy R") (pin "11") (pinfunction "11_11") (pintype "passive"))
    )
    (net (code "144") (name "unconnected-(Teensy R-Pad12)") (class "Default")
      (node (ref "Teensy R") (pin "12") (pinfunction "12_12") (pintype "passive"))
    )
    (net (code "145") (name "unconnected-(Teensy R-Pad13)") (class "Default")
      (node (ref "Teensy R") (pin "13") (pinfunction "13_13") (pintype "passive"))
    )
    (net (code "146") (name "unconnected-(Teensy R-Pad16)") (class "Default")
      (node (ref "Teensy R") (pin "16") (pinfunction "16_16") (pintype "passive"))
    )
    (net (code "147") (name "unconnected-(Teensy R-Pad17)") (class "Default")
      (node (ref "Teensy R") (pin "17") (pinfunction "17_17") (pintype "passive"))
    )
    (net (code "148") (name "unconnected-(Teensy R-Pad18)") (class "Default")
      (node (ref "Teensy R") (pin "18") (pinfunction "18_18") (pintype "passive"))
    )
    (net (code "149") (name "unconnected-(Teensy R-Pad19)") (class "Default")
      (node (ref "Teensy R") (pin "19") (pinfunction "19_19") (pintype "passive"))
    )
    (net (code "150") (name "unconnected-(Teensy R-Pad20)") (class "Default")
      (node (ref "Teensy R") (pin "20") (pinfunction "20_20") (pintype "passive"))
    )
    (net (code "151") (name "unconnected-(Teensy R-Pad21)") (class "Default")
      (node (ref "Teensy R") (pin "21") (pinfunction "21_21") (pintype "passive"))
    )
    (net (code "152") (name "unconnected-(Teensy R-Pad22)") (class "Default")
      (node (ref "Teensy R") (pin "22") (pinfunction "22_22") (pintype "passive"))
    )
    (net (code "153") (name "unconnected-(Teensy R-Pad23)") (class "Default")
      (node (ref "Teensy R") (pin "23") (pinfunction "23_23") (pintype "passive"))
    )
    (net (code "154") (name "unconnected-(Teensy R-Pad24)") (class "Default")
      (node (ref "Teensy R") (pin "24") (pinfunction "24_24") (pintype "passive"))
    )
  )
)
